# Arduino_Leonardo-REV3b.net
KiCad netlist of a schematic drawn in EAGLE
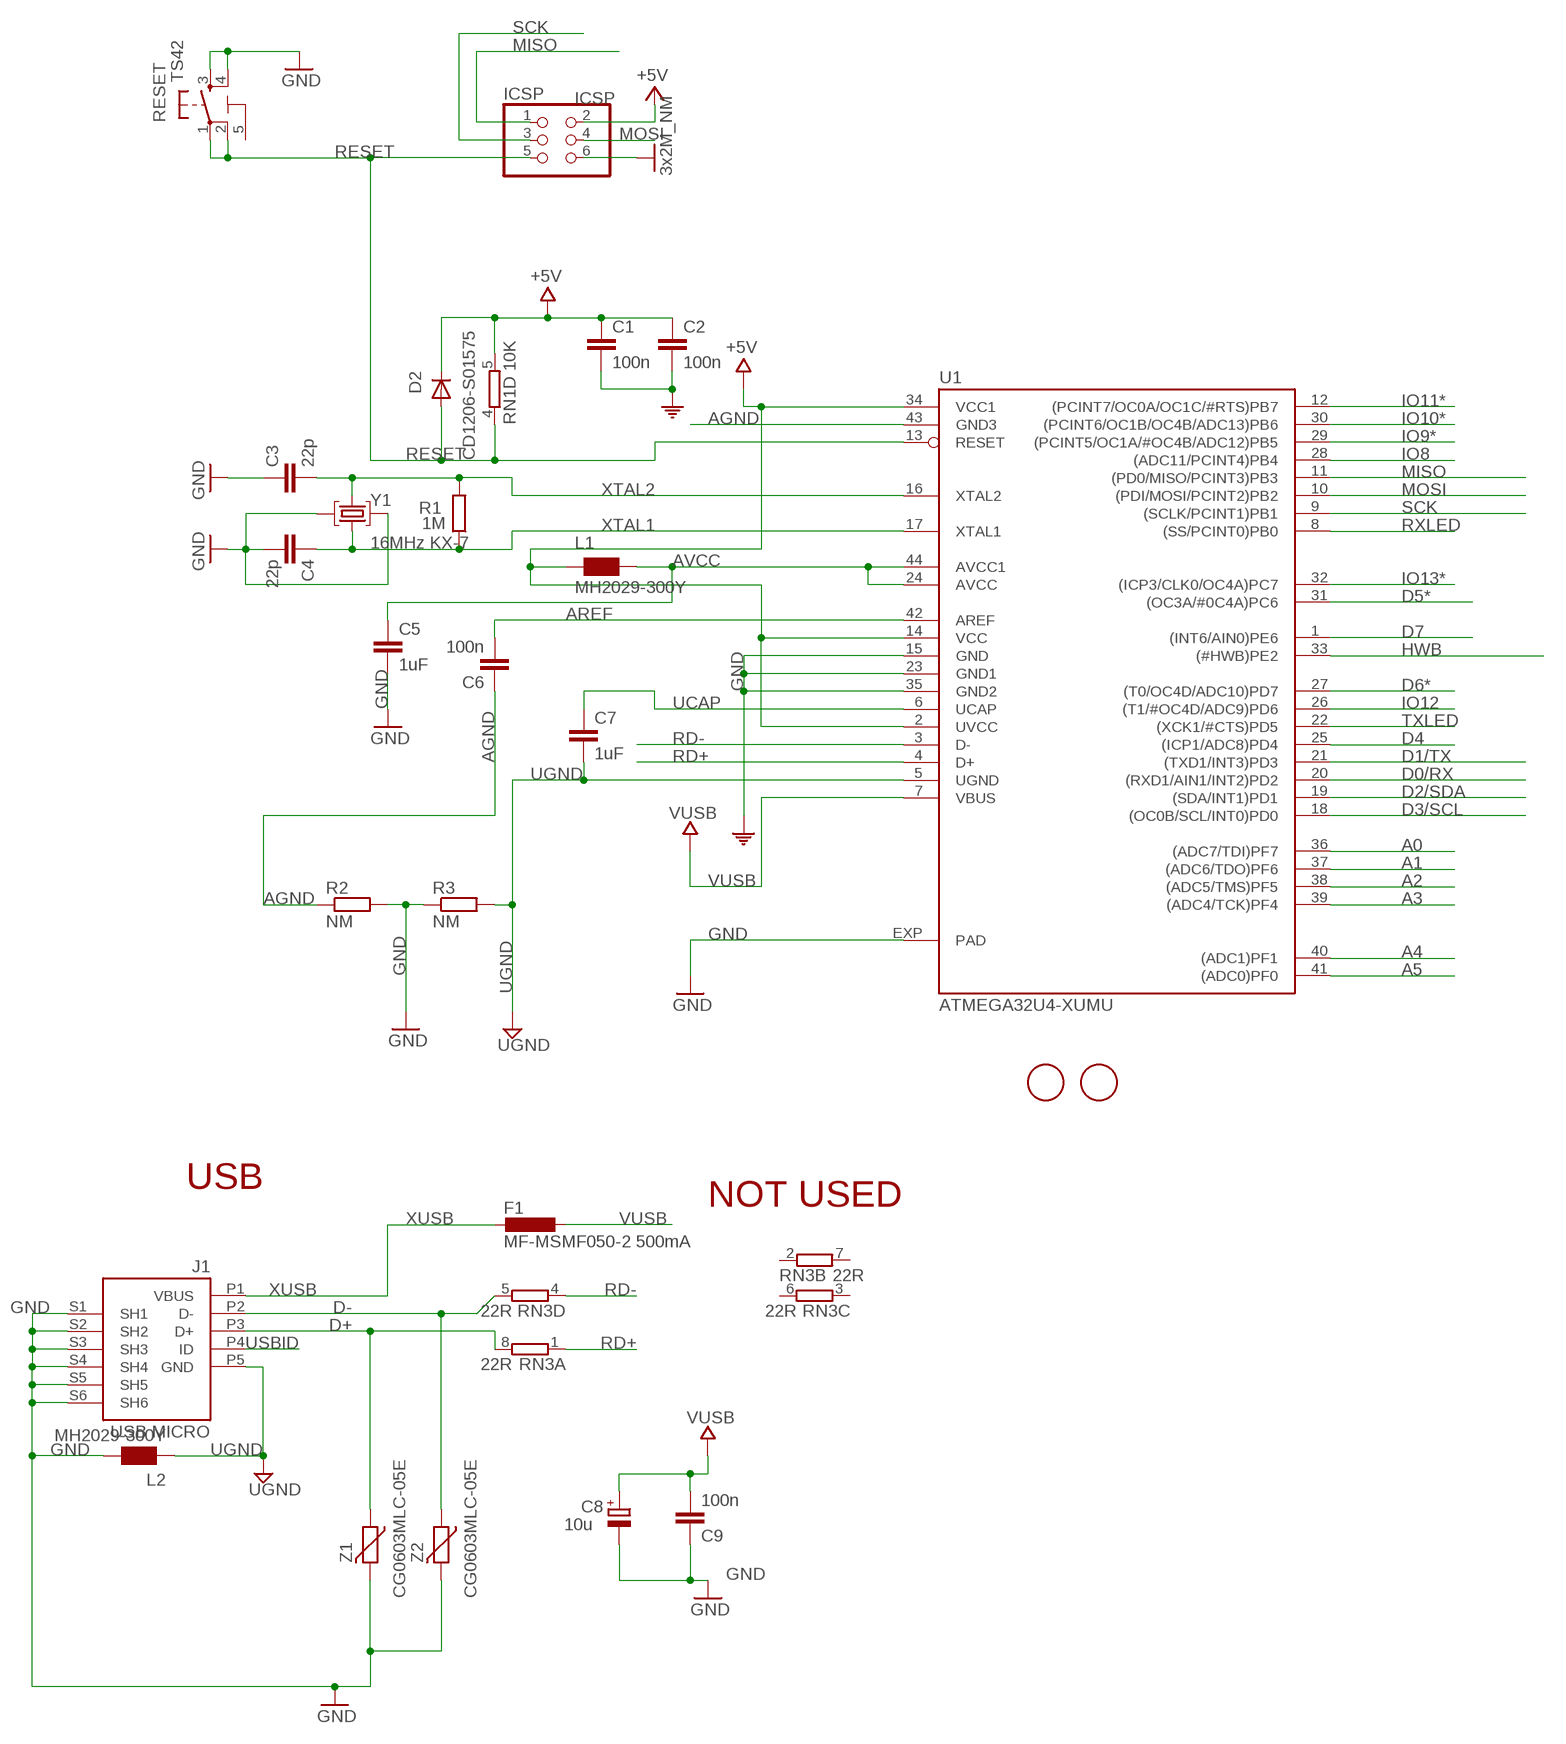
[diagram p0: schematic, sheet 1, part 1 of 2]
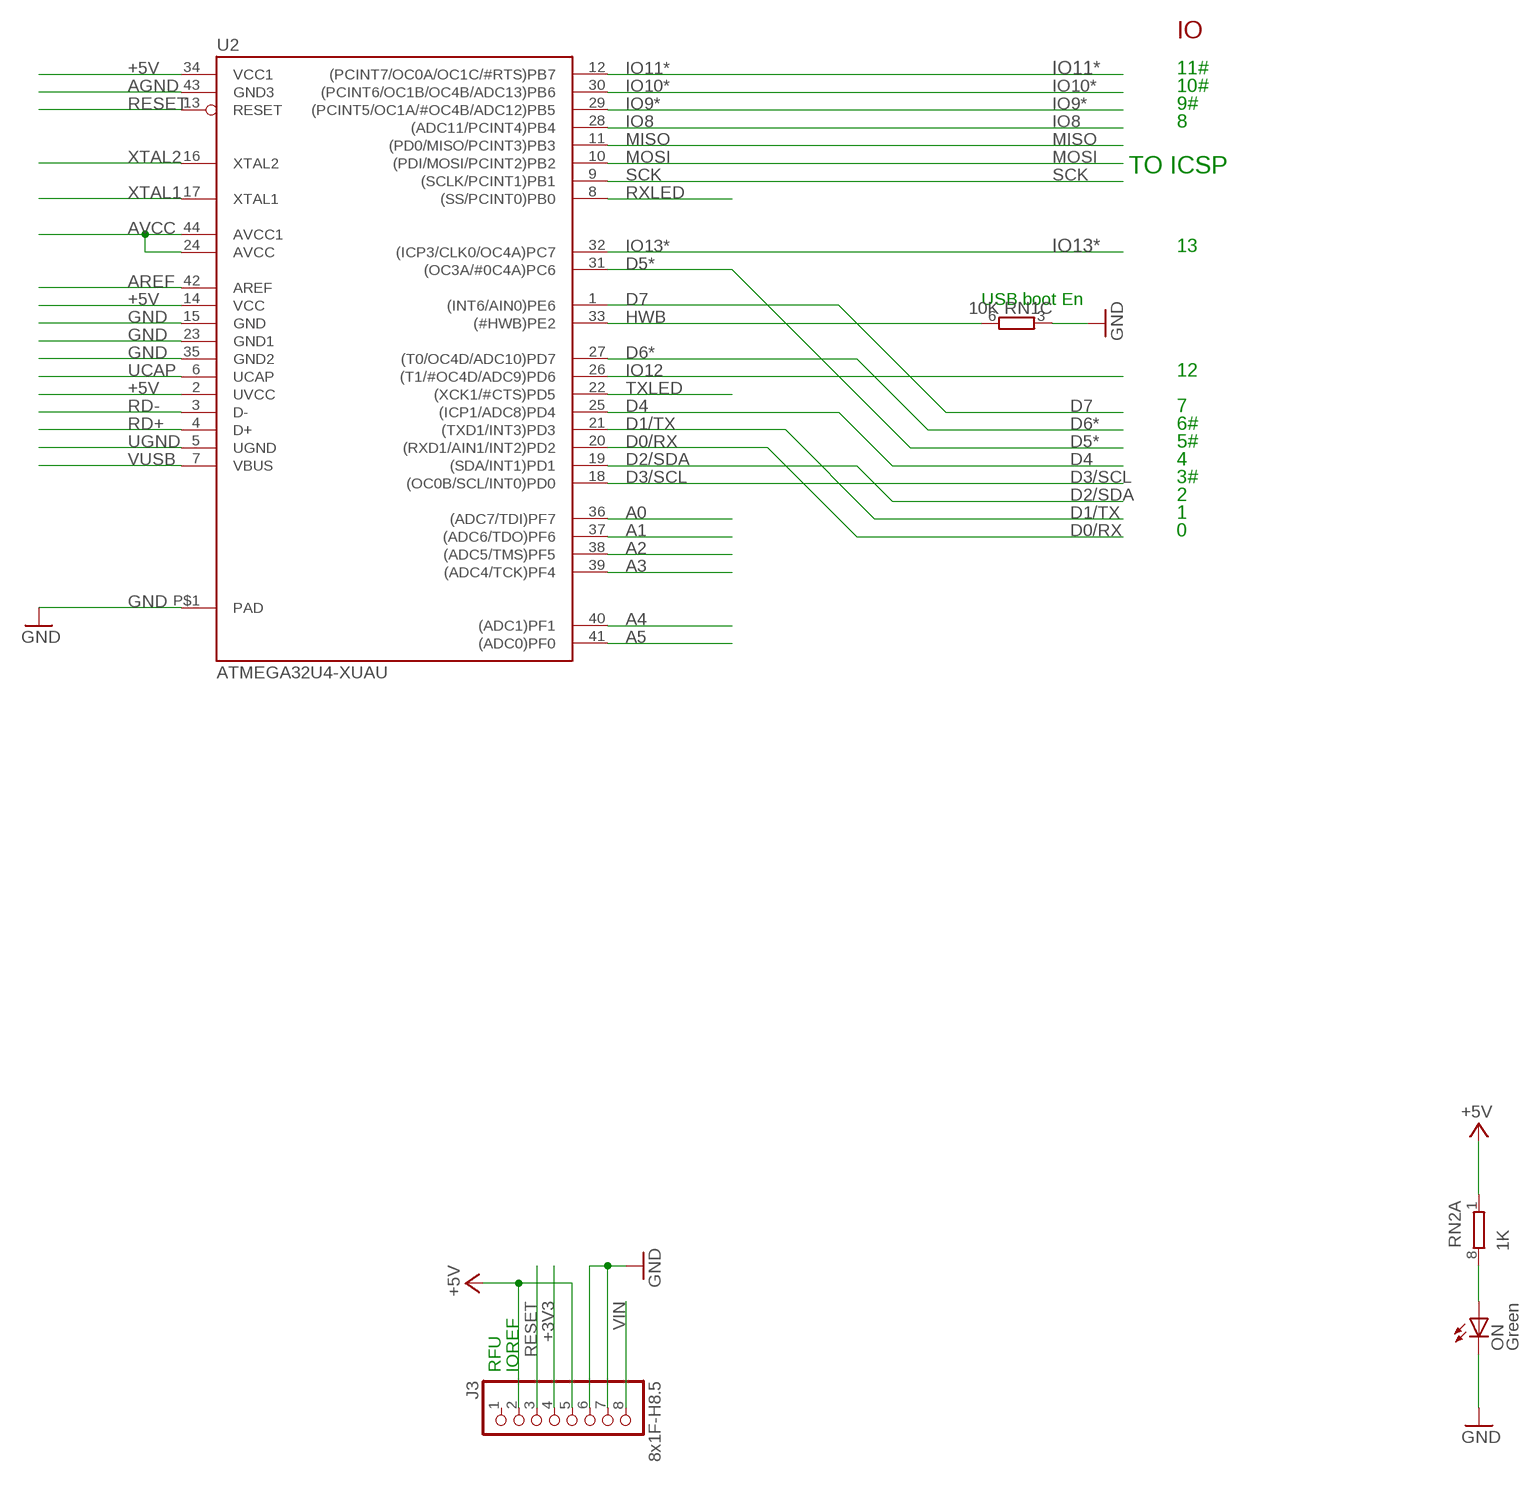
[diagram p1: schematic, sheet 1, part 2 of 2]

(export (version "E")
  (design (tool "Eeschema 10.0.6"))
  (components
    (comp (ref "C1")
      (value "100n")
      (footprint "eagle-import:C0603-ROUND")
      (libsource (lib "eagle-import") (part "C-EUC0603"))
    )
    (comp (ref "C2")
      (value "100n")
      (footprint "eagle-import:C0603-ROUND")
      (libsource (lib "eagle-import") (part "C-EUC0603"))
    )
    (comp (ref "C3")
      (value "22p")
      (footprint "eagle-import:C0603-ROUND")
      (libsource (lib "eagle-import") (part "C-EUC0603"))
    )
    (comp (ref "C4")
      (value "22p")
      (footprint "eagle-import:C0603-ROUND")
      (libsource (lib "eagle-import") (part "C-EUC0603"))
    )
    (comp (ref "C5")
      (value "1uF")
      (footprint "eagle-import:C0603-ROUND")
      (libsource (lib "eagle-import") (part "C-EUC0603"))
    )
    (comp (ref "C6")
      (value "100n")
      (footprint "eagle-import:C0603-ROUND")
      (libsource (lib "eagle-import") (part "C-EUC0603"))
    )
    (comp (ref "C7")
      (value "1uF")
      (footprint "eagle-import:C0603-ROUND")
      (libsource (lib "eagle-import") (part "C-EUC0603"))
    )
    (comp (ref "C8")
      (value "10u")
      (footprint "eagle-import:SMC_B")
      (libsource (lib "eagle-import") (part "CPOL-EUSMCB"))
    )
    (comp (ref "C9")
      (value "100n")
      (footprint "eagle-import:C0603-ROUND")
      (libsource (lib "eagle-import") (part "C-EUC0603"))
    )
    (comp (ref "D2")
      (value "CD1206-S01575")
      (footprint "eagle-import:MINIMELF")
      (libsource (lib "eagle-import") (part "DIODE-MINIMELF"))
    )
    (comp (ref "F1")
      (value "MF-MSMF050-2 500mA")
      (footprint "eagle-import:L1812")
      (libsource (lib "eagle-import") (part "L-EUL1812"))
    )
    (comp (ref "FID1")
      (value "FIDUCIALMOUNT")
      (footprint "eagle-import:FIDUCIA-MOUNT")
      (libsource (lib "eagle-import") (part "FIDUCIALMOUNT"))
    )
    (comp (ref "FID2")
      (value "FIDUCIALMOUNT")
      (footprint "eagle-import:FIDUCIA-MOUNT")
      (libsource (lib "eagle-import") (part "FIDUCIALMOUNT"))
    )
    (comp (ref "ICSP")
      (value "ICSP")
      (footprint "eagle-import:2X03")
      (libsource (lib "eagle-import") (part "PINHD-2X3"))
    )
    (comp (ref "J1")
      (value "USB MICRO")
      (footprint "eagle-import:CON2_USB_MICRO_B_AT")
      (libsource (lib "eagle-import") (part "MYCON2_USB-MINI-B"))
    )
    (comp (ref "J3")
      (value "8x1F-H8.5")
      (footprint "eagle-import:1X08")
      (libsource (lib "eagle-import") (part "PINHD-1X8"))
    )
    (comp (ref "L1")
      (value "MH2029-300Y")
      (footprint "eagle-import:0805")
      (libsource (lib "eagle-import") (part "WE-CBF_0805"))
    )
    (comp (ref "L2")
      (value "MH2029-300Y")
      (footprint "eagle-import:0805")
      (libsource (lib "eagle-import") (part "WE-CBF_0805"))
    )
    (comp (ref "ON")
      (value "Green")
      (footprint "eagle-import:CHIPLED_0805")
      (libsource (lib "eagle-import") (part "LEDCHIPLED_0805"))
    )
    (comp (ref "R1")
      (value "1M")
      (footprint "eagle-import:R0603-ROUND")
      (libsource (lib "eagle-import") (part "R-EU_R0603"))
    )
    (comp (ref "R2")
      (value "NM")
      (footprint "eagle-import:R0402")
      (libsource (lib "eagle-import") (part "R-EU_R0402"))
    )
    (comp (ref "R3")
      (value "NM")
      (footprint "eagle-import:R0402")
      (libsource (lib "eagle-import") (part "R-EU_R0402"))
    )
    (comp (ref "RESET")
      (value "TS42")
      (footprint "eagle-import:TS42")
      (libsource (lib "eagle-import") (part "TS42"))
    )
    (comp (ref "RN1")
      (value "10K")
      (footprint "eagle-import:CAY16")
      (libsource (lib "eagle-import") (part "4R-NCAY16"))
    )
    (comp (ref "RN2")
      (value "1K")
      (footprint "eagle-import:CAY16")
      (libsource (lib "eagle-import") (part "4R-NCAY16"))
    )
    (comp (ref "RN3")
      (value "22R")
      (footprint "eagle-import:CAY16")
      (libsource (lib "eagle-import") (part "4R-NCAY16"))
    )
    (comp (ref "U1")
      (value "ATMEGA32U4-XUMU")
      (footprint "eagle-import:QFN44ML7X7")
      (libsource (lib "eagle-import") (part "ATMEGA32U4-XUMU"))
    )
    (comp (ref "U2")
      (value "ATMEGA32U4-XUAU")
      (footprint "eagle-import:TQFP44-PAD")
      (libsource (lib "eagle-import") (part "ATMEGA32U4-XUAU"))
    )
    (comp (ref "Y1")
      (value "16MHz KX-7")
      (footprint "eagle-import:CRYSTAL-3.2-2.5")
      (libsource (lib "eagle-import") (part "CRYSTAL-3.2-2.5"))
    )
    (comp (ref "Z1")
      (value "CG0603MLC-05E")
      (footprint "eagle-import:CT_CN0603")
      (libsource (lib "eagle-import") (part "VARISTORCN0603"))
    )
    (comp (ref "Z2")
      (value "CG0603MLC-05E")
      (footprint "eagle-import:CT_CN0603")
      (libsource (lib "eagle-import") (part "VARISTORCN0603"))
    )
  )
  (nets
    (net (code "1") (name "+5V") (class "Default")
      (node (ref "C1") (pin "1") (pinfunction "1_1") (pintype "passive"))
      (node (ref "C2") (pin "1") (pinfunction "1_1") (pintype "passive"))
      (node (ref "D2") (pin "C") (pinfunction "C_C") (pintype "passive"))
      (node (ref "ICSP") (pin "2") (pinfunction "2_2") (pintype "passive"))
      (node (ref "J3") (pin "2") (pinfunction "2_2") (pintype "passive"))
      (node (ref "J3") (pin "5") (pinfunction "5_5") (pintype "passive"))
      (node (ref "L1") (pin "1") (pinfunction "1_1") (pintype "passive"))
      (node (ref "RN1") (pin "5") (pinfunction "2_5") (pintype "passive"))
      (node (ref "RN2") (pin "1") (pinfunction "1_1") (pintype "passive"))
      (node (ref "U1") (pin "14") (pinfunction "VCC_14") (pintype "power_in"))
      (node (ref "U1") (pin "2") (pinfunction "UVCC_2") (pintype "power_in"))
      (node (ref "U1") (pin "34") (pinfunction "VCC1_34") (pintype "power_in"))
      (node (ref "U2") (pin "14") (pinfunction "VCC_14") (pintype "power_in"))
      (node (ref "U2") (pin "2") (pinfunction "UVCC_2") (pintype "power_in"))
      (node (ref "U2") (pin "34") (pinfunction "VCC1_34") (pintype "power_in"))
    )
    (net (code "2") (name "/+3V3") (class "Default")
      (node (ref "J3") (pin "4") (pinfunction "4_4") (pintype "passive"))
    )
    (net (code "3") (name "/5-GND") (class "Default")
      (node (ref "RESET") (pin "5") (pinfunction "5-GND_5") (pintype "power_in"))
    )
    (net (code "4") (name "/A0") (class "Default")
      (node (ref "U1") (pin "36") (pinfunction "(ADC7/TDI)PF7_36") (pintype "bidirectional"))
      (node (ref "U2") (pin "36") (pinfunction "(ADC7/TDI)PF7_36") (pintype "bidirectional"))
    )
    (net (code "5") (name "/A1") (class "Default")
      (node (ref "U1") (pin "37") (pinfunction "(ADC6/TDO)PF6_37") (pintype "bidirectional"))
      (node (ref "U2") (pin "37") (pinfunction "(ADC6/TDO)PF6_37") (pintype "bidirectional"))
    )
    (net (code "6") (name "/A2") (class "Default")
      (node (ref "U1") (pin "38") (pinfunction "(ADC5/TMS)PF5_38") (pintype "bidirectional"))
      (node (ref "U2") (pin "38") (pinfunction "(ADC5/TMS)PF5_38") (pintype "bidirectional"))
    )
    (net (code "7") (name "/A3") (class "Default")
      (node (ref "U1") (pin "39") (pinfunction "(ADC4/TCK)PF4_39") (pintype "bidirectional"))
      (node (ref "U2") (pin "39") (pinfunction "(ADC4/TCK)PF4_39") (pintype "bidirectional"))
    )
    (net (code "8") (name "/A4") (class "Default")
      (node (ref "U1") (pin "40") (pinfunction "(ADC1)PF1_40") (pintype "bidirectional"))
      (node (ref "U2") (pin "40") (pinfunction "(ADC1)PF1_40") (pintype "bidirectional"))
    )
    (net (code "9") (name "/A5") (class "Default")
      (node (ref "U1") (pin "41") (pinfunction "(ADC0)PF0_41") (pintype "bidirectional"))
      (node (ref "U2") (pin "41") (pinfunction "(ADC0)PF0_41") (pintype "bidirectional"))
    )
    (net (code "10") (name "/AGND") (class "Default")
      (node (ref "C6") (pin "1") (pinfunction "1_1") (pintype "passive"))
      (node (ref "R2") (pin "1") (pinfunction "1_1") (pintype "passive"))
      (node (ref "U1") (pin "43") (pinfunction "GND3_43") (pintype "power_in"))
      (node (ref "U2") (pin "43") (pinfunction "GND3_43") (pintype "power_in"))
    )
    (net (code "11") (name "/AREF") (class "Default")
      (node (ref "C6") (pin "2") (pinfunction "2_2") (pintype "passive"))
      (node (ref "U1") (pin "42") (pinfunction "AREF_42") (pintype "power_in"))
      (node (ref "U2") (pin "42") (pinfunction "AREF_42") (pintype "power_in"))
    )
    (net (code "12") (name "/AVCC") (class "Default")
      (node (ref "C5") (pin "1") (pinfunction "1_1") (pintype "passive"))
      (node (ref "L1") (pin "2") (pinfunction "2_2") (pintype "passive"))
      (node (ref "U1") (pin "24") (pinfunction "AVCC_24") (pintype "power_in"))
      (node (ref "U1") (pin "44") (pinfunction "AVCC1_44") (pintype "power_in"))
      (node (ref "U2") (pin "24") (pinfunction "AVCC_24") (pintype "power_in"))
      (node (ref "U2") (pin "44") (pinfunction "AVCC1_44") (pintype "power_in"))
    )
    (net (code "13") (name "/D+") (class "Default")
      (node (ref "J1") (pin "P3") (pinfunction "D+_P3") (pintype "bidirectional"))
      (node (ref "RN3") (pin "8") (pinfunction "2_8") (pintype "passive"))
      (node (ref "Z1") (pin "1") (pinfunction "1_1") (pintype "passive"))
    )
    (net (code "14") (name "/D-") (class "Default")
      (node (ref "J1") (pin "P2") (pinfunction "D-_P2") (pintype "bidirectional"))
      (node (ref "RN3") (pin "5") (pinfunction "2_5") (pintype "passive"))
      (node (ref "Z2") (pin "1") (pinfunction "1_1") (pintype "passive"))
    )
    (net (code "15") (name "/D0{slash}RX") (class "Default")
      (node (ref "U1") (pin "20") (pinfunction "(RXD1/AIN1/INT2)PD2_20") (pintype "bidirectional"))
      (node (ref "U2") (pin "20") (pinfunction "(RXD1/AIN1/INT2)PD2_20") (pintype "bidirectional"))
    )
    (net (code "16") (name "/D1{slash}TX") (class "Default")
      (node (ref "U1") (pin "21") (pinfunction "(TXD1/INT3)PD3_21") (pintype "bidirectional"))
      (node (ref "U2") (pin "21") (pinfunction "(TXD1/INT3)PD3_21") (pintype "bidirectional"))
    )
    (net (code "17") (name "/D2{slash}SDA") (class "Default")
      (node (ref "U1") (pin "19") (pinfunction "(SDA/INT1)PD1_19") (pintype "bidirectional"))
      (node (ref "U2") (pin "19") (pinfunction "(SDA/INT1)PD1_19") (pintype "bidirectional"))
    )
    (net (code "18") (name "/D3{slash}SCL") (class "Default")
      (node (ref "U1") (pin "18") (pinfunction "(OC0B/SCL/INT0)PD0_18") (pintype "bidirectional"))
      (node (ref "U2") (pin "18") (pinfunction "(OC0B/SCL/INT0)PD0_18") (pintype "bidirectional"))
    )
    (net (code "19") (name "/D4") (class "Default")
      (node (ref "U1") (pin "25") (pinfunction "(ICP1/ADC8)PD4_25") (pintype "bidirectional"))
      (node (ref "U2") (pin "25") (pinfunction "(ICP1/ADC8)PD4_25") (pintype "bidirectional"))
    )
    (net (code "20") (name "/D5*") (class "Default")
      (node (ref "U1") (pin "31") (pinfunction "(OC3A/#0C4A)PC6_31") (pintype "bidirectional"))
      (node (ref "U2") (pin "31") (pinfunction "(OC3A/#0C4A)PC6_31") (pintype "bidirectional"))
    )
    (net (code "21") (name "/D6*") (class "Default")
      (node (ref "U1") (pin "27") (pinfunction "(T0/OC4D/ADC10)PD7_27") (pintype "bidirectional"))
      (node (ref "U2") (pin "27") (pinfunction "(T0/OC4D/ADC10)PD7_27") (pintype "bidirectional"))
    )
    (net (code "22") (name "/D7") (class "Default")
      (node (ref "U1") (pin "1") (pinfunction "(INT6/AIN0)PE6_1") (pintype "bidirectional"))
      (node (ref "U2") (pin "1") (pinfunction "(INT6/AIN0)PE6_1") (pintype "bidirectional"))
    )
    (net (code "23") (name "/HWB") (class "Default")
      (node (ref "RN1") (pin "6") (pinfunction "2_6") (pintype "passive"))
      (node (ref "U1") (pin "33") (pinfunction "(#HWB)PE2_33") (pintype "bidirectional"))
      (node (ref "U2") (pin "33") (pinfunction "(#HWB)PE2_33") (pintype "bidirectional"))
    )
    (net (code "24") (name "/IO8") (class "Default")
      (node (ref "U1") (pin "28") (pinfunction "(ADC11/PCINT4)PB4_28") (pintype "bidirectional"))
      (node (ref "U2") (pin "28") (pinfunction "(ADC11/PCINT4)PB4_28") (pintype "bidirectional"))
    )
    (net (code "25") (name "/IO9*") (class "Default")
      (node (ref "U1") (pin "29") (pinfunction "(PCINT5/OC1A/#OC4B/ADC12)PB5_29") (pintype "bidirectional"))
      (node (ref "U2") (pin "29") (pinfunction "(PCINT5/OC1A/#OC4B/ADC12)PB5_29") (pintype "bidirectional"))
    )
    (net (code "26") (name "/IO10*") (class "Default")
      (node (ref "U1") (pin "30") (pinfunction "(PCINT6/OC1B/OC4B/ADC13)PB6_30") (pintype "bidirectional"))
      (node (ref "U2") (pin "30") (pinfunction "(PCINT6/OC1B/OC4B/ADC13)PB6_30") (pintype "bidirectional"))
    )
    (net (code "27") (name "/IO11*") (class "Default")
      (node (ref "U1") (pin "12") (pinfunction "(PCINT7/OC0A/OC1C/#RTS)PB7_12") (pintype "bidirectional"))
      (node (ref "U2") (pin "12") (pinfunction "(PCINT7/OC0A/OC1C/#RTS)PB7_12") (pintype "bidirectional"))
    )
    (net (code "28") (name "/IO12") (class "Default")
      (node (ref "U1") (pin "26") (pinfunction "(T1/#OC4D/ADC9)PD6_26") (pintype "bidirectional"))
      (node (ref "U2") (pin "26") (pinfunction "(T1/#OC4D/ADC9)PD6_26") (pintype "bidirectional"))
    )
    (net (code "29") (name "/IO13*") (class "Default")
      (node (ref "U1") (pin "32") (pinfunction "(ICP3/CLK0/OC4A)PC7_32") (pintype "bidirectional"))
      (node (ref "U2") (pin "32") (pinfunction "(ICP3/CLK0/OC4A)PC7_32") (pintype "bidirectional"))
    )
    (net (code "30") (name "/MISO") (class "Default")
      (node (ref "ICSP") (pin "1") (pinfunction "1_1") (pintype "passive"))
      (node (ref "U1") (pin "11") (pinfunction "(PD0/MISO/PCINT3)PB3_11") (pintype "bidirectional"))
      (node (ref "U2") (pin "11") (pinfunction "(PD0/MISO/PCINT3)PB3_11") (pintype "bidirectional"))
    )
    (net (code "31") (name "/MOSI") (class "Default")
      (node (ref "ICSP") (pin "4") (pinfunction "4_4") (pintype "passive"))
      (node (ref "U1") (pin "10") (pinfunction "(PDI/MOSI/PCINT2)PB2_10") (pintype "bidirectional"))
      (node (ref "U2") (pin "10") (pinfunction "(PDI/MOSI/PCINT2)PB2_10") (pintype "bidirectional"))
    )
    (net (code "32") (name "/RD+") (class "Default")
      (node (ref "RN3") (pin "1") (pinfunction "1_1") (pintype "passive"))
      (node (ref "U1") (pin "4") (pinfunction "D+_4") (pintype "bidirectional"))
      (node (ref "U2") (pin "4") (pinfunction "D+_4") (pintype "bidirectional"))
    )
    (net (code "33") (name "/RD-") (class "Default")
      (node (ref "RN3") (pin "4") (pinfunction "1_4") (pintype "passive"))
      (node (ref "U1") (pin "3") (pinfunction "D-_3") (pintype "bidirectional"))
      (node (ref "U2") (pin "3") (pinfunction "D-_3") (pintype "bidirectional"))
    )
    (net (code "34") (name "/RESET") (class "Default")
      (node (ref "D2") (pin "A") (pinfunction "A_A") (pintype "passive"))
      (node (ref "ICSP") (pin "5") (pinfunction "5_5") (pintype "passive"))
      (node (ref "J3") (pin "3") (pinfunction "3_3") (pintype "passive"))
      (node (ref "RESET") (pin "1") (pinfunction "1_1") (pintype "passive"))
      (node (ref "RESET") (pin "2") (pinfunction "2_2") (pintype "passive"))
      (node (ref "RN1") (pin "4") (pinfunction "1_4") (pintype "passive"))
      (node (ref "U1") (pin "13") (pinfunction "RESET_13") (pintype "input"))
      (node (ref "U2") (pin "13") (pinfunction "RESET_13") (pintype "input"))
    )
    (net (code "35") (name "/RXLED") (class "Default")
      (node (ref "U1") (pin "8") (pinfunction "(SS/PCINT0)PB0_8") (pintype "bidirectional"))
      (node (ref "U2") (pin "8") (pinfunction "(SS/PCINT0)PB0_8") (pintype "bidirectional"))
    )
    (net (code "36") (name "/SCK") (class "Default")
      (node (ref "ICSP") (pin "3") (pinfunction "3_3") (pintype "passive"))
      (node (ref "U1") (pin "9") (pinfunction "(SCLK/PCINT1)PB1_9") (pintype "bidirectional"))
      (node (ref "U2") (pin "9") (pinfunction "(SCLK/PCINT1)PB1_9") (pintype "bidirectional"))
    )
    (net (code "37") (name "/TXLED") (class "Default")
      (node (ref "U1") (pin "22") (pinfunction "(XCK1/#CTS)PD5_22") (pintype "bidirectional"))
      (node (ref "U2") (pin "22") (pinfunction "(XCK1/#CTS)PD5_22") (pintype "bidirectional"))
    )
    (net (code "38") (name "/UCAP") (class "Default")
      (node (ref "C7") (pin "1") (pinfunction "1_1") (pintype "passive"))
      (node (ref "U1") (pin "6") (pinfunction "UCAP_6") (pintype "passive"))
      (node (ref "U2") (pin "6") (pinfunction "UCAP_6") (pintype "passive"))
    )
    (net (code "39") (name "/USBID") (class "Default")
      (node (ref "J1") (pin "P4") (pinfunction "ID_P4") (pintype "bidirectional"))
    )
    (net (code "40") (name "/VIN") (class "Default")
      (node (ref "J3") (pin "8") (pinfunction "8_8") (pintype "passive"))
    )
    (net (code "41") (name "/XTAL1") (class "Default")
      (node (ref "C4") (pin "1") (pinfunction "1_1") (pintype "passive"))
      (node (ref "R1") (pin "1") (pinfunction "1_1") (pintype "passive"))
      (node (ref "U1") (pin "17") (pinfunction "XTAL1_17") (pintype "bidirectional"))
      (node (ref "U2") (pin "17") (pinfunction "XTAL1_17") (pintype "bidirectional"))
      (node (ref "Y1") (pin "1") (pinfunction "C1_1") (pintype "passive"))
    )
    (net (code "42") (name "/XTAL2") (class "Default")
      (node (ref "C3") (pin "2") (pinfunction "2_2") (pintype "passive"))
      (node (ref "R1") (pin "2") (pinfunction "2_2") (pintype "passive"))
      (node (ref "U1") (pin "16") (pinfunction "XTAL2_16") (pintype "bidirectional"))
      (node (ref "U2") (pin "16") (pinfunction "XTAL2_16") (pintype "bidirectional"))
      (node (ref "Y1") (pin "3") (pinfunction "C2_3") (pintype "passive"))
    )
    (net (code "43") (name "/XUSB") (class "Default")
      (node (ref "F1") (pin "2") (pinfunction "2_2") (pintype "passive"))
      (node (ref "J1") (pin "P1") (pinfunction "VBUS_P1") (pintype "power_in"))
    )
    (net (code "44") (name "3x2M_NM") (class "Default")
      (node (ref "C1") (pin "2") (pinfunction "2_2") (pintype "passive"))
      (node (ref "C2") (pin "2") (pinfunction "2_2") (pintype "passive"))
      (node (ref "C3") (pin "1") (pinfunction "1_1") (pintype "passive"))
      (node (ref "C4") (pin "2") (pinfunction "2_2") (pintype "passive"))
      (node (ref "C5") (pin "2") (pinfunction "2_2") (pintype "passive"))
      (node (ref "C8") (pin "-") (pinfunction "-_-") (pintype "passive"))
      (node (ref "C9") (pin "1") (pinfunction "1_1") (pintype "passive"))
      (node (ref "ICSP") (pin "6") (pinfunction "6_6") (pintype "passive"))
      (node (ref "J1") (pin "S1") (pinfunction "SH1_S1") (pintype "passive"))
      (node (ref "J1") (pin "S2") (pinfunction "SH2_S2") (pintype "passive"))
      (node (ref "J1") (pin "S3") (pinfunction "SH3_S3") (pintype "passive"))
      (node (ref "J1") (pin "S4") (pinfunction "SH4_S4") (pintype "passive"))
      (node (ref "J1") (pin "S5") (pinfunction "SH5_S5") (pintype "passive"))
      (node (ref "J1") (pin "S6") (pinfunction "SH6_S6") (pintype "passive"))
      (node (ref "J3") (pin "6") (pinfunction "6_6") (pintype "passive"))
      (node (ref "J3") (pin "7") (pinfunction "7_7") (pintype "passive"))
      (node (ref "L2") (pin "2") (pinfunction "2_2") (pintype "passive"))
      (node (ref "ON") (pin "C") (pinfunction "C_C") (pintype "passive"))
      (node (ref "R2") (pin "2") (pinfunction "2_2") (pintype "passive"))
      (node (ref "R3") (pin "1") (pinfunction "1_1") (pintype "passive"))
      (node (ref "RESET") (pin "3") (pinfunction "3_3") (pintype "passive"))
      (node (ref "RESET") (pin "4") (pinfunction "4_4") (pintype "passive"))
      (node (ref "RN1") (pin "3") (pinfunction "1_3") (pintype "passive"))
      (node (ref "U1") (pin "15") (pinfunction "GND_15") (pintype "power_in"))
      (node (ref "U1") (pin "23") (pinfunction "GND1_23") (pintype "power_in"))
      (node (ref "U1") (pin "35") (pinfunction "GND2_35") (pintype "power_in"))
      (node (ref "U1") (pin "EXP") (pinfunction "PAD_EXP") (pintype "power_in"))
      (node (ref "U2") (pin "15") (pinfunction "GND_15") (pintype "power_in"))
      (node (ref "U2") (pin "23") (pinfunction "GND1_23") (pintype "power_in"))
      (node (ref "U2") (pin "35") (pinfunction "GND2_35") (pintype "power_in"))
      (node (ref "U2") (pin "P$1") (pinfunction "PAD_P$1") (pintype "power_in"))
      (node (ref "Y1") (pin "2") (pinfunction "GND_2") (pintype "passive"))
      (node (ref "Y1") (pin "4") (pinfunction "GND_4") (pintype "passive"))
      (node (ref "Z1") (pin "2") (pinfunction "2_2") (pintype "passive"))
      (node (ref "Z2") (pin "2") (pinfunction "2_2") (pintype "passive"))
    )
    (net (code "45") (name "Net-(RN2A-2)") (class "Default")
      (node (ref "ON") (pin "A") (pinfunction "A_A") (pintype "passive"))
      (node (ref "RN2") (pin "8") (pinfunction "2_8") (pintype "passive"))
    )
    (net (code "46") (name "UGND") (class "Default")
      (node (ref "C7") (pin "2") (pinfunction "2_2") (pintype "passive"))
      (node (ref "J1") (pin "P5") (pinfunction "GND_P5") (pintype "passive"))
      (node (ref "L2") (pin "1") (pinfunction "1_1") (pintype "passive"))
      (node (ref "R3") (pin "2") (pinfunction "2_2") (pintype "passive"))
      (node (ref "U1") (pin "5") (pinfunction "UGND_5") (pintype "power_in"))
      (node (ref "U2") (pin "5") (pinfunction "UGND_5") (pintype "power_in"))
    )
    (net (code "47") (name "VUSB") (class "Default")
      (node (ref "C8") (pin "+") (pinfunction "+_+") (pintype "passive"))
      (node (ref "C9") (pin "2") (pinfunction "2_2") (pintype "passive"))
      (node (ref "F1") (pin "1") (pinfunction "1_1") (pintype "passive"))
      (node (ref "U1") (pin "7") (pinfunction "VBUS_7") (pintype "input"))
      (node (ref "U2") (pin "7") (pinfunction "VBUS_7") (pintype "input"))
    )
    (net (code "48") (name "unconnected-(J3-Pad1)") (class "Default")
      (node (ref "J3") (pin "1") (pinfunction "1_1") (pintype "passive"))
    )
    (net (code "49") (name "unconnected-(RN3B-1-Pad2)") (class "Default")
      (node (ref "RN3") (pin "2") (pinfunction "1_2") (pintype "passive"))
    )
    (net (code "50") (name "unconnected-(RN3B-2-Pad7)") (class "Default")
      (node (ref "RN3") (pin "7") (pinfunction "2_7") (pintype "passive"))
    )
    (net (code "51") (name "unconnected-(RN3C-1-Pad3)") (class "Default")
      (node (ref "RN3") (pin "3") (pinfunction "1_3") (pintype "passive"))
    )
    (net (code "52") (name "unconnected-(RN3C-2-Pad6)") (class "Default")
      (node (ref "RN3") (pin "6") (pinfunction "2_6") (pintype "passive"))
    )
  )
)
